# Schematic_Sheet_1.net
KiCad netlist of a schematic drawn in Altium Designer
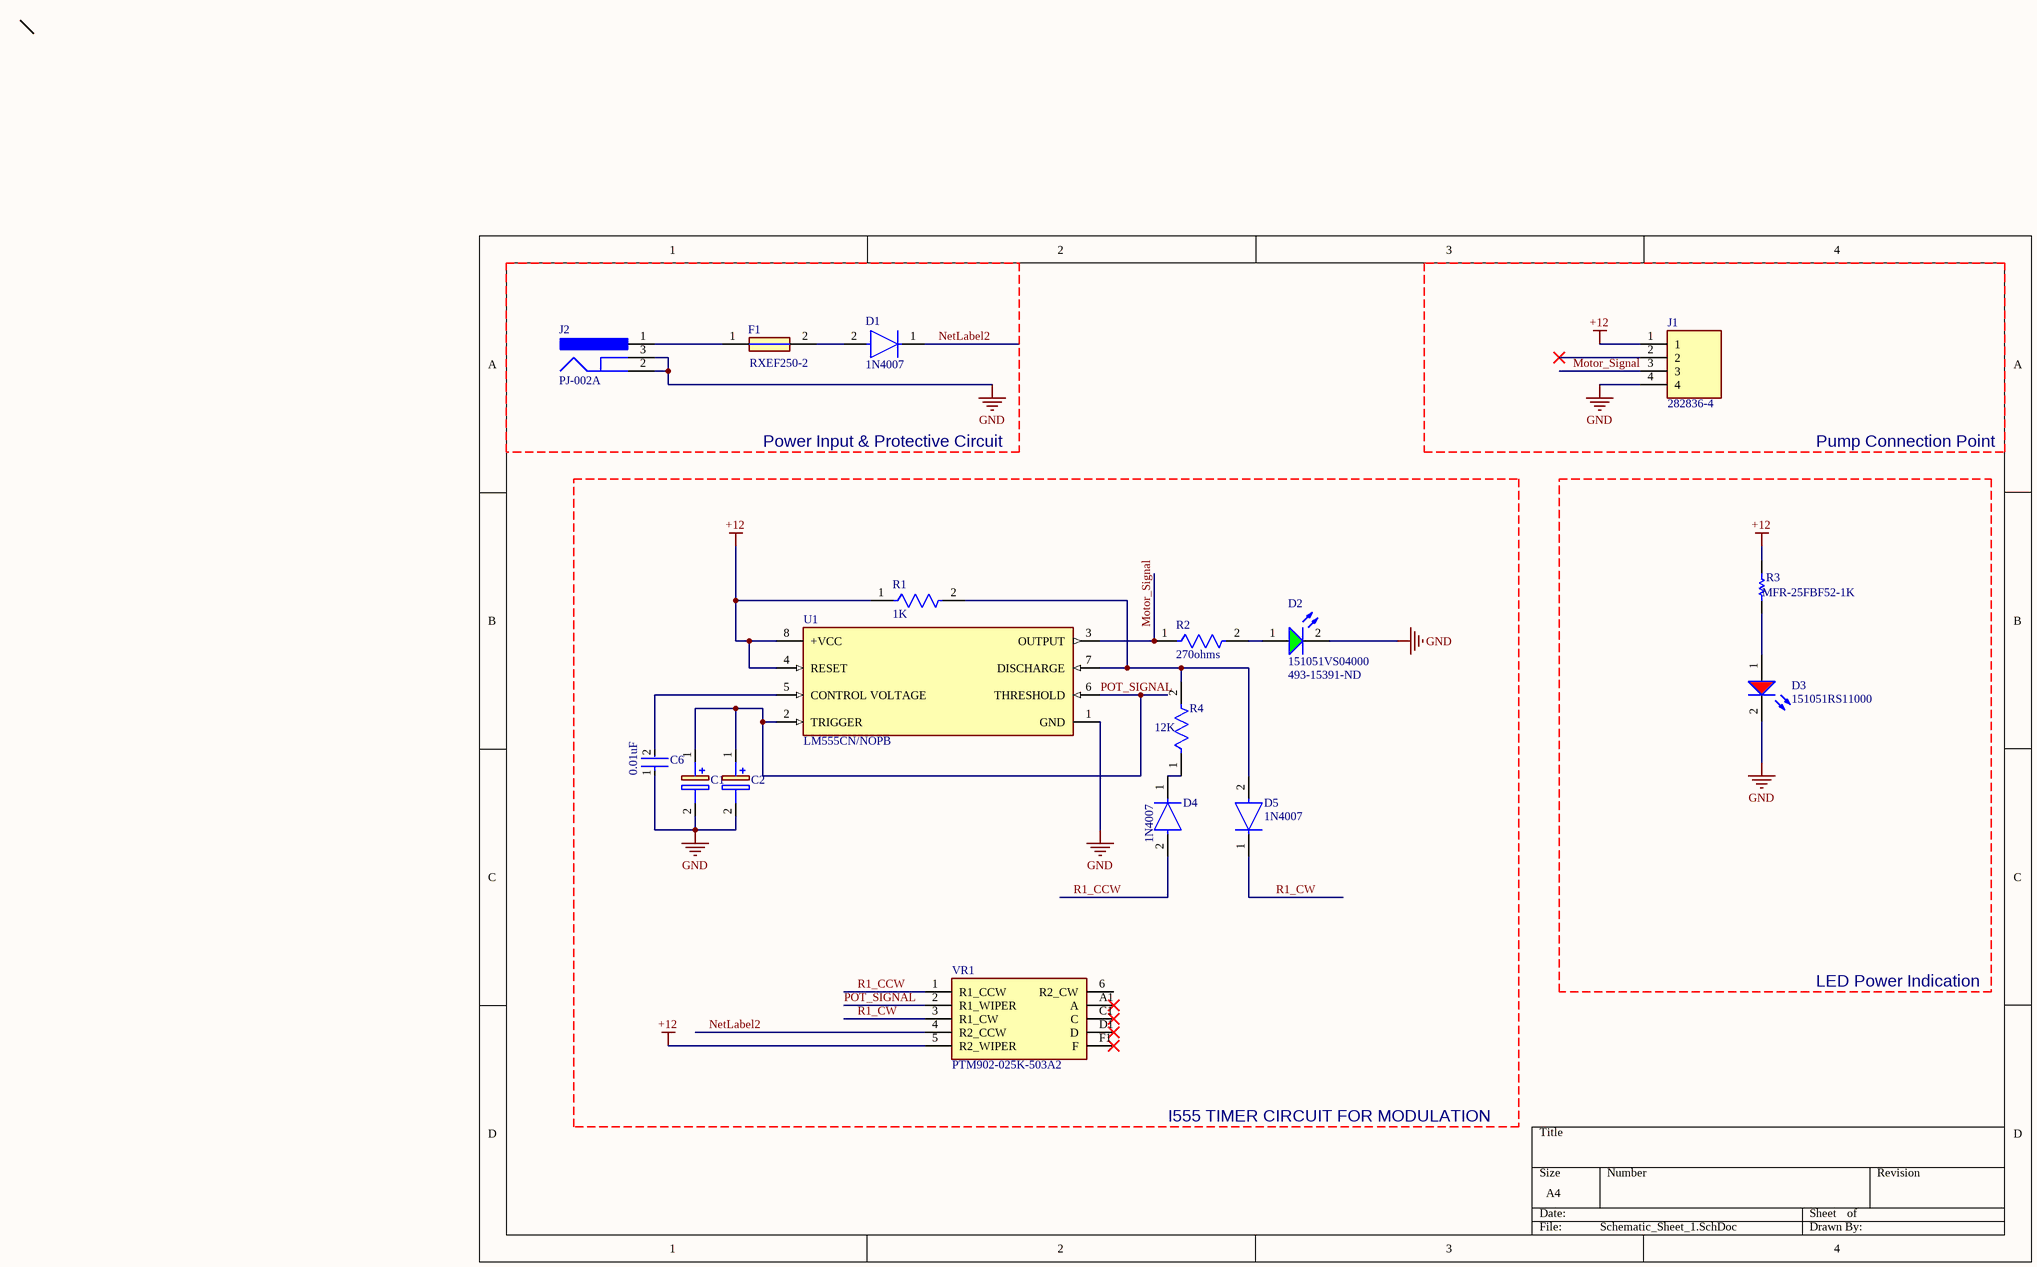
[diagram p0: Schematic_Sheet_1.SchDoc]

(export (version "E")
  (design (tool "Eeschema 10.0.6"))
  (components
    (comp (ref "C1")
      (value "ESH106M050AC3AA")
      (footprint "SamacSys:ESH106M050AC3AA")
      (description "Aluminium Electrolytic Capacitors - Radial Leaded 50V 10uF 105C 2k Hour Radial")
      (fields (field (name "MOUSER PART NUMBER") "80-ESH106M050AC3AA"))
      (libsource (lib "*") (part "ESH106M050AC3AA"))
    )
    (comp (ref "C2")
      (value "ESH106M050AC3AA")
      (footprint "SamacSys:ESH106M050AC3AA")
      (description "Aluminium Electrolytic Capacitors - Radial Leaded 50V 10uF 105C 2k Hour Radial")
      (fields (field (name "MOUSER PART NUMBER") "80-ESH106M050AC3AA"))
      (libsource (lib "*") (part "ESH106M050AC3AA"))
    )
    (comp (ref "C6")
      (value "0.01uF")
      (footprint "FP-C410C104M5U5TA7200-MFG")
      (description "CAP CER 0.1UF 50V Z5U AXIAL")
      (fields (field (name "TOLERANCE") "20%"))
      (libsource (lib "Altium Content Vault") (part "b4654b650e69147ec39a6b967a45e02"))
    )
    (comp (ref "D1")
      (value "1N4007")
      (footprint "FP-1N4007-MFG")
      (description "Rectifier diode 1000 V 1 A DO-41, ,")
      (fields
        (field (name "MANUFACTURER") "Diotec")
        (field (name "OCTOPART") "https://octopart.com/1n4007-diotec-4040411")
      )
      (libsource (lib "Altium Content Vault") (part "d7152d700b627762746794eb795d46e"))
    )
    (comp (ref "D2")
      (value "151051VS04000")
      (footprint "WL-TMRC_D5.9H8.7")
      (fields
        (field (name "SUPPLIER PART NUMBER 1") "493-15391-ND")
        (field (name "MANUFACTURER") "Nichicon")
        (field (name "MANUFACTURER PART NUMBER") "UKL1HR15KDDANA")
        (field (name "TOLERANCE") "10%")
      )
      (libsource (lib "Altium Content Vault") (part "LED_Green_1A-2K"))
    )
    (comp (ref "D3")
      (value "151051RS11000")
      (footprint "WL-TMRC_D5.9H8.7")
      (libsource (lib "Altium Content Vault") (part "LED_Red_1A-2K"))
    )
    (comp (ref "D4")
      (value "1N4007")
      (footprint "FP-1N4007-MFG")
      (description "Rectifier diode 1000 V 1 A DO-41, ,")
      (fields
        (field (name "MANUFACTURER") "Diotec")
        (field (name "OCTOPART") "https://octopart.com/1n4007-diotec-4040411")
      )
      (libsource (lib "Altium Content Vault") (part "d7152d700b627762746794eb795d46e"))
    )
    (comp (ref "D5")
      (value "1N4007")
      (footprint "FP-1N4007-MFG")
      (description "Rectifier diode 1000 V 1 A DO-41, ,")
      (fields
        (field (name "MANUFACTURER") "Diotec")
        (field (name "OCTOPART") "https://octopart.com/1n4007-diotec-4040411")
      )
      (libsource (lib "Altium Content Vault") (part "d7152d700b627762746794eb795d46e"))
    )
    (comp (ref "F1")
      (value "RXEF250-2")
      (footprint "SamacSys:RXEF2502")
      (description "Fuse")
      (fields (field (name "MOUSER PART NUMBER") "650-RXEF250-2"))
      (libsource (lib "*") (part "RXEF250-2"))
    )
    (comp (ref "J1")
      (value "282836-4")
      (footprint "SamacSys:2828364")
      (description "Connector")
      (fields (field (name "MOUSER PART NUMBER") "571-2828364"))
      (libsource (lib "*") (part "282836-4"))
    )
    (comp (ref "J2")
      (value "PJ-002A")
      (footprint "CUI-PJ-002A_V")
      (fields (field (name "MANUFACTURER") "CUIInc."))
      (libsource (lib "Altium Content Vault") (part "JACK-2CD3-RN_B"))
    )
    (comp (ref "R1")
      (value "1K")
      (footprint "FP-MRS1600-MFG")
      (description "RES 20K OHM 0.4W 1% AXIAL")
      (fields (field (name "TOLERANCE") "1%"))
      (libsource (lib "Altium Content Vault") (part "1029c3af85768c4190bb7ad29bc67b5"))
    )
    (comp (ref "R2")
      (value "270ohms")
      (footprint "FP-MRS1600-MFG")
      (description "RES 20K OHM 0.4W 1% AXIAL")
      (fields (field (name "TOLERANCE") "1%"))
      (libsource (lib "Altium Content Vault") (part "1029c3af85768c4190bb7ad29bc67b5"))
    )
    (comp (ref "R3")
      (value "MFR-25FBF52-1K")
      (footprint "RESA60-630X240")
      (description "Axial Resistor, 1 KOhm, +/- 1%, 0.25W, -55 to 155 degC, 2-Pin THD, RoHS, Bulk")
      (fields (field (name "TOLERANCE") "1%"))
      (libsource (lib "Altium Content Vault") (part "RES-2"))
    )
    (comp (ref "R4")
      (value "12K")
      (footprint "FP-MRS1600-MFG")
      (description "RES 20K OHM 0.4W 1% AXIAL")
      (fields (field (name "TOLERANCE") "1%"))
      (libsource (lib "Altium Content Vault") (part "1029c3af85768c4190bb7ad29bc67b5"))
    )
    (comp (ref "U1")
      (value "LM555CN/NOPB")
      (footprint "FP-P0008A-MFG")
      (description "IC OSC SINGLE TIMER 100KHZ 8-DIP")
      (fields
        (field (name "MANUFACTURER") "Texas Instruments")
        (field (name "OCTOPART") "https://octopart.com/lm555cn%2Fnopb-texas+instruments-24814897")
      )
      (libsource (lib "Altium Content Vault") (part "8056d98efc272addb90effbbf338635"))
    )
    (comp (ref "VR1")
      (value "PTM902-025K-503A2")
      (footprint "SamacSys:PTM902025K503A2")
      (description "Variable Resistor")
      (fields (field (name "MOUSER PART NUMBER") "652-PTM902-025K503A2"))
      (libsource (lib "*") (part "PTM902-025K-503A2"))
    )
  )
  (nets
    (net (code "1") (name "+12") (class "Default")
      (node (ref "J1") (pin "1") (pinfunction "1_1") (pintype "passive"))
      (node (ref "R1") (pin "1") (pinfunction "1_1") (pintype "passive"))
      (node (ref "R3") (pin "1") (pinfunction "1_1") (pintype "passive"))
      (node (ref "U1") (pin "4") (pinfunction "RESET_4") (pintype "input"))
      (node (ref "U1") (pin "8") (pinfunction "+VCC_8") (pintype "power_in"))
      (node (ref "VR1") (pin "5") (pinfunction "R2_WIPER_5") (pintype "passive"))
    )
    (net (code "2") (name "/Motor_Signal") (class "Default")
      (node (ref "J1") (pin "3") (pinfunction "3_3") (pintype "passive"))
      (node (ref "R2") (pin "1") (pinfunction "1_1") (pintype "passive"))
      (node (ref "U1") (pin "3") (pinfunction "OUTPUT_3") (pintype "output"))
    )
    (net (code "3") (name "/NetLabel2") (class "Default")
      (node (ref "D1") (pin "1") (pinfunction "C_1") (pintype "passive"))
      (node (ref "VR1") (pin "4") (pinfunction "R2_CCW_4") (pintype "passive"))
    )
    (net (code "4") (name "/POT_SIGNAL") (class "Default")
      (node (ref "C1") (pin "1") (pinfunction "+_1") (pintype "passive"))
      (node (ref "C2") (pin "1") (pinfunction "+_1") (pintype "passive"))
      (node (ref "U1") (pin "2") (pinfunction "TRIGGER_2") (pintype "input"))
      (node (ref "U1") (pin "6") (pinfunction "THRESHOLD_6") (pintype "input"))
      (node (ref "VR1") (pin "2") (pinfunction "R1_WIPER_2") (pintype "passive"))
    )
    (net (code "5") (name "/R1_CCW") (class "Default")
      (node (ref "D4") (pin "2") (pinfunction "A_2") (pintype "passive"))
      (node (ref "VR1") (pin "1") (pinfunction "R1_CCW_1") (pintype "passive"))
    )
    (net (code "6") (name "/R1_CW") (class "Default")
      (node (ref "D5") (pin "1") (pinfunction "C_1") (pintype "passive"))
      (node (ref "VR1") (pin "3") (pinfunction "R1_CW_3") (pintype "passive"))
    )
    (net (code "7") (name "GND") (class "Default")
      (node (ref "C1") (pin "2") (pinfunction "-_2") (pintype "passive"))
      (node (ref "C2") (pin "2") (pinfunction "-_2") (pintype "passive"))
      (node (ref "C6") (pin "1") (pinfunction "1_1") (pintype "passive"))
      (node (ref "D2") (pin "2") (pinfunction "K_2") (pintype "passive"))
      (node (ref "D3") (pin "2") (pinfunction "K_2") (pintype "passive"))
      (node (ref "J1") (pin "4") (pinfunction "4_4") (pintype "passive"))
      (node (ref "J2") (pin "2") (pinfunction "2_2") (pintype "passive"))
      (node (ref "J2") (pin "3") (pinfunction "3_3") (pintype "passive"))
      (node (ref "U1") (pin "1") (pinfunction "GND_1") (pintype "power_in"))
    )
    (net (code "8") (name "Net-(D1-A)") (class "Default")
      (node (ref "D1") (pin "2") (pinfunction "A_2") (pintype "passive"))
      (node (ref "F1") (pin "2") (pinfunction "2_2") (pintype "passive"))
    )
    (net (code "9") (name "Net-(D2-A)") (class "Default")
      (node (ref "D2") (pin "1") (pinfunction "A_1") (pintype "passive"))
      (node (ref "R2") (pin "2") (pinfunction "2_2") (pintype "passive"))
    )
    (net (code "10") (name "Net-(D3-A)") (class "Default")
      (node (ref "D3") (pin "1") (pinfunction "A_1") (pintype "passive"))
      (node (ref "R3") (pin "2") (pinfunction "2_2") (pintype "passive"))
    )
    (net (code "11") (name "Net-(D4-C)") (class "Default")
      (node (ref "D4") (pin "1") (pinfunction "C_1") (pintype "passive"))
      (node (ref "R4") (pin "1") (pinfunction "1_1") (pintype "passive"))
    )
    (net (code "12") (name "Net-(D5-A)") (class "Default")
      (node (ref "D5") (pin "2") (pinfunction "A_2") (pintype "passive"))
      (node (ref "R1") (pin "2") (pinfunction "2_2") (pintype "passive"))
      (node (ref "R4") (pin "2") (pinfunction "2_2") (pintype "passive"))
      (node (ref "U1") (pin "7") (pinfunction "DISCHARGE_7") (pintype "input"))
    )
    (net (code "13") (name "Net-(F1-Pad1)") (class "Default")
      (node (ref "F1") (pin "1") (pinfunction "1_1") (pintype "passive"))
      (node (ref "J2") (pin "1") (pinfunction "1_1") (pintype "passive"))
    )
    (net (code "14") (name "Net-(U1-CONTROL_VOLTAGE)") (class "Default")
      (node (ref "C6") (pin "2") (pinfunction "2_2") (pintype "passive"))
      (node (ref "U1") (pin "5") (pinfunction "CONTROL_VOLTAGE_5") (pintype "input"))
    )
    (net (code "15") (name "unconnected-(J1-Pad2)") (class "Default")
      (node (ref "J1") (pin "2") (pinfunction "2_2") (pintype "passive+no_connect"))
    )
    (net (code "16") (name "unconnected-(VR1-A-PadA1)") (class "Default")
      (node (ref "VR1") (pin "A1") (pinfunction "A_A1") (pintype "passive+no_connect"))
    )
    (net (code "17") (name "unconnected-(VR1-C-PadC1)") (class "Default")
      (node (ref "VR1") (pin "C1") (pinfunction "C_C1") (pintype "passive+no_connect"))
    )
    (net (code "18") (name "unconnected-(VR1-D-PadD1)") (class "Default")
      (node (ref "VR1") (pin "D1") (pinfunction "D_D1") (pintype "passive+no_connect"))
    )
    (net (code "19") (name "unconnected-(VR1-F-PadF1)") (class "Default")
      (node (ref "VR1") (pin "F1") (pinfunction "F_F1") (pintype "passive+no_connect"))
    )
    (net (code "20") (name "unconnected-(VR1-R2_CW-Pad6)") (class "Default")
      (node (ref "VR1") (pin "6") (pinfunction "R2_CW_6") (pintype "passive"))
    )
  )
)
